# temp_sensor.net
KiCad netlist of a schematic drawn in Altium Designer
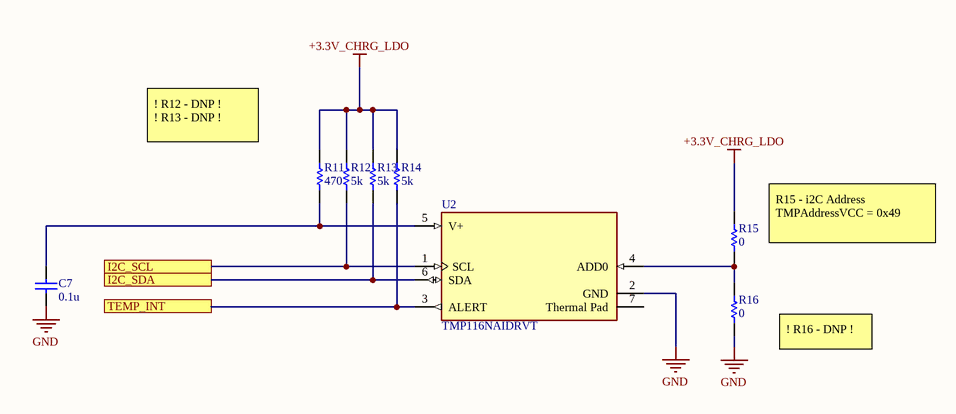
[diagram p0: temp_sensor.SchDoc]

(export (version "E")
  (design (tool "Eeschema 10.0.6"))
  (components
    (comp (ref "C7")
      (value "0.1u")
      (footprint "CAPC2013X145X50LL20T25")
      (description "C0805C104Z5VACTU")
      (fields (field (name "MANUFACTURER") "Kemet"))
      (libsource (lib "Altium Content Vault") (part "CAP"))
    )
    (comp (ref "R11")
      (value "470")
      (footprint "RESC2013X70X40LL20T20")
      (description "ERJ-6GEYJ471V")
      (fields (field (name "MANUFACTURER") "Panasonic"))
      (libsource (lib "Altium Content Vault") (part "RES"))
    )
    (comp (ref "R12")
      (value "5k")
      (footprint "RESC2013X70X40LL20T20")
      (description "2012")
      (fields (field (name "PART NUMBER") "ERJ-6GEYJ471V") (field (name "MANUFACTURER") "Panasonic"))
      (libsource (lib "Altium Content Vault") (part "RES"))
    )
    (comp (ref "R13")
      (value "5k")
      (footprint "RESC2013X70X40LL20T20")
      (description "2012")
      (fields (field (name "PART NUMBER") "ERJ-6GEYJ471V") (field (name "MANUFACTURER") "Panasonic"))
      (libsource (lib "Altium Content Vault") (part "RES"))
    )
    (comp (ref "R14")
      (value "5k")
      (footprint "RESC2013X70X40LL20T20")
      (description "2012")
      (fields (field (name "PART NUMBER") "ERJ-6GEYJ471V") (field (name "MANUFACTURER") "Panasonic"))
      (libsource (lib "Altium Content Vault") (part "RES"))
    )
    (comp (ref "R15")
      (value "0")
      (footprint "RESC2013X70X40LL20T20")
      (description "2012")
      (fields (field (name "PART NUMBER") "ERJ-6GEYJ471V") (field (name "MANUFACTURER") "Panasonic"))
      (libsource (lib "Altium Content Vault") (part "RES"))
    )
    (comp (ref "R16")
      (value "0")
      (footprint "RESC2013X70X40LL20T20")
      (description "2012")
      (fields (field (name "PART NUMBER") "ERJ-6GEYJ471V") (field (name "MANUFACTURER") "Panasonic"))
      (libsource (lib "Altium Content Vault") (part "RES"))
    )
    (comp (ref "U2")
      (value "TMP116NAIDRVT")
      (footprint "FP-DRV0006A-MFG")
      (description "SENSOR DIGITAL -55C-125C 6WSON")
      (fields
        (field (name "MANUFACTURER") "Texas Instruments")
        (field (name "OCTOPART") "https://octopart.com/tmp116naidrvt-texas+instruments-82367759")
      )
      (libsource (lib "Altium Content Vault") (part "2fad53bed00cb42ac2b52aea1ae4b02"))
    )
  )
  (nets
    (net (code "1") (name "+3.3V_CHRG_LDO") (class "Default")
      (node (ref "R11") (pin "2") (pinfunction "2_2") (pintype "passive"))
      (node (ref "R12") (pin "2") (pinfunction "2_2") (pintype "passive"))
      (node (ref "R13") (pin "2") (pinfunction "2_2") (pintype "passive"))
      (node (ref "R14") (pin "2") (pinfunction "2_2") (pintype "passive"))
      (node (ref "R15") (pin "2") (pinfunction "2_2") (pintype "passive"))
    )
    (net (code "2") (name "/I2C_SCL") (class "Default")
      (node (ref "R12") (pin "1") (pinfunction "1_1") (pintype "passive"))
      (node (ref "U2") (pin "1") (pinfunction "SCL_1") (pintype "input"))
    )
    (net (code "3") (name "/I2C_SDA") (class "Default")
      (node (ref "R13") (pin "1") (pinfunction "1_1") (pintype "passive"))
      (node (ref "U2") (pin "6") (pinfunction "SDA_6") (pintype "bidirectional"))
    )
    (net (code "4") (name "/TEMP_INT") (class "Default")
      (node (ref "R14") (pin "1") (pinfunction "1_1") (pintype "passive"))
      (node (ref "U2") (pin "3") (pinfunction "ALERT_3") (pintype "output"))
    )
    (net (code "5") (name "GND") (class "Default")
      (node (ref "C7") (pin "1") (pinfunction "1_1") (pintype "passive"))
      (node (ref "R16") (pin "1") (pinfunction "1_1") (pintype "passive"))
      (node (ref "U2") (pin "2") (pinfunction "GND_2") (pintype "power_in"))
    )
    (net (code "6") (name "Net-(U2-ADD0)") (class "Default")
      (node (ref "R15") (pin "1") (pinfunction "1_1") (pintype "passive"))
      (node (ref "R16") (pin "2") (pinfunction "2_2") (pintype "passive"))
      (node (ref "U2") (pin "4") (pinfunction "ADD0_4") (pintype "input"))
    )
    (net (code "7") (name "Net-(U2-V+)") (class "Default")
      (node (ref "C7") (pin "2") (pinfunction "2_2") (pintype "passive"))
      (node (ref "R11") (pin "1") (pinfunction "1_1") (pintype "passive"))
      (node (ref "U2") (pin "5") (pinfunction "V+_5") (pintype "input"))
    )
    (net (code "8") (name "unconnected-(U2-Thermal_Pad-Pad7)") (class "Default")
      (node (ref "U2") (pin "7") (pinfunction "Thermal_Pad_7") (pintype "power_in"))
    )
  )
)
